# SCH_HABSat2_schematic_2023-01-31.net
KiCad netlist of a schematic drawn in EasyEDA
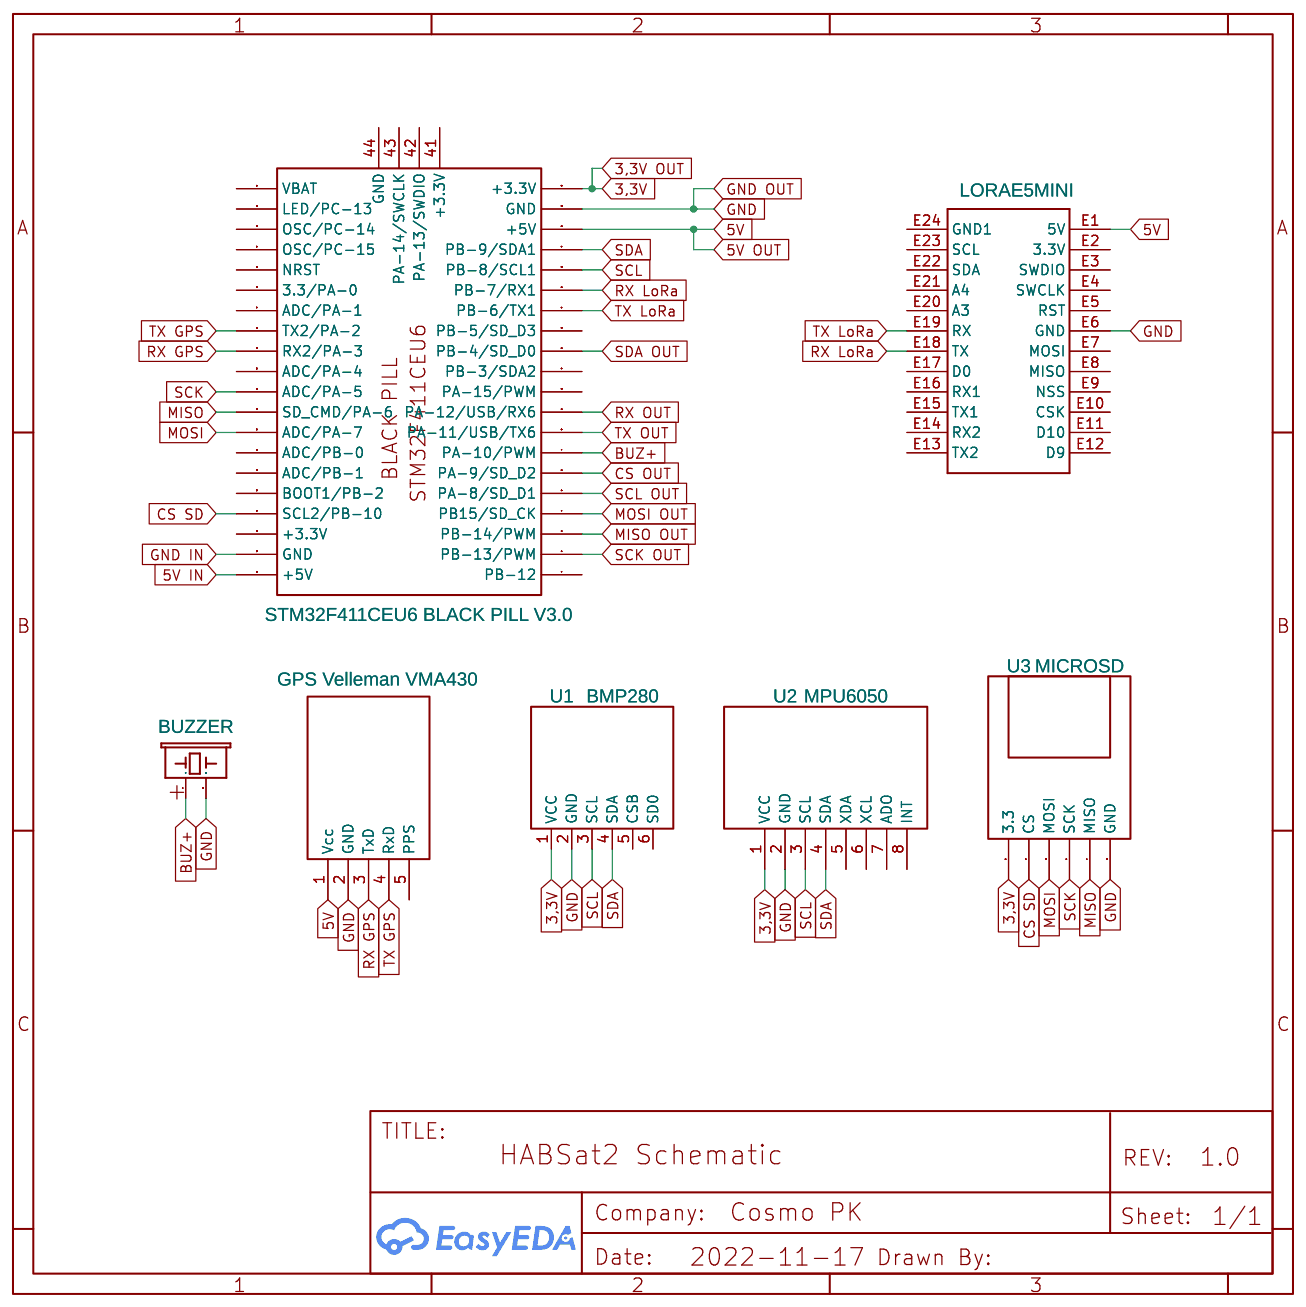
[diagram p0: schematic sheet]

(export (version "E")
  (design (tool "Eeschema 10.0.6"))
  (components
    (comp (ref "1") (value "LORAE5MINI") (libsource (lib "") (part "LORAE5MINI")))
    (comp (ref "SG1") (value "BUZZER") (libsource (lib "") (part "BUZZER KX-12MM")))
    (comp (ref "STM1")
      (value "STM32F411CEU6 BLACK PILL V3.0")
      (libsource (lib "") (part "STM32F411CEU6 BLACK PILL V3.0"))
    )
    (comp (ref "U1")
      (value "BMP280")
      (fields (field (name "BOM_Manufacturer Part") "GY-BMP280"))
      (libsource (lib "") (part "GY-BMP280"))
    )
    (comp (ref "U2") (value "MPU6050") (libsource (lib "") (part "MPU6050")))
    (comp (ref "U3") (value "MICROSD") (libsource (lib "") (part "MICROSD")))
    (comp (ref "VCC")
      (value "GPS Velleman VMA430")
      (fields (field (name "BOM_Manufacturer Part") "VMA430"))
      (libsource (lib "") (part "GPS Velleman VMA430"))
    )
  )
  (nets
    (net (code "1") (name "3,3V") (class "Default")
      (node (ref "STM1") (pin "20") (pinfunction "+3.3V_20") (pintype "unspecified"))
      (node (ref "U1") (pin "1") (pinfunction "VCC_1") (pintype "unspecified"))
      (node (ref "U2") (pin "1") (pinfunction "VCC_1") (pintype "unspecified"))
      (node (ref "U3") (pin "5") (pinfunction "3.3_5") (pintype "unspecified"))
    )
    (net (code "2") (name "5V") (class "Default")
      (node (ref "1") (pin "E1") (pinfunction "5V_E1") (pintype "bidirectional"))
      (node (ref "STM1") (pin "18") (pinfunction "+5V_18") (pintype "unspecified"))
      (node (ref "VCC") (pin "1") (pinfunction "Vcc_1") (pintype "unspecified"))
    )
    (net (code "3") (name "5V IN") (class "Default")
      (node (ref "STM1") (pin "40") (pinfunction "+5V_40") (pintype "unspecified"))
    )
    (net (code "4") (name "BUZ+") (class "Default")
      (node (ref "SG1") (pin "1") (pinfunction "1_1") (pintype "unspecified"))
      (node (ref "STM1") (pin "7") (pinfunction "PA-10/PWM_7") (pintype "unspecified"))
    )
    (net (code "5") (name "CS OUT") (class "Default")
      (node (ref "STM1") (pin "6") (pinfunction "PA-9/SD_D2_6") (pintype "unspecified"))
    )
    (net (code "6") (name "CS SD") (class "Default")
      (node (ref "STM1") (pin "37") (pinfunction "SCL2/PB-10_37") (pintype "unspecified"))
      (node (ref "U3") (pin "1") (pinfunction "CS_1") (pintype "unspecified"))
    )
    (net (code "7") (name "GND") (class "Default")
      (node (ref "1") (pin "E6") (pinfunction "GND_E6") (pintype "bidirectional"))
      (node (ref "SG1") (pin "2") (pinfunction "2_2") (pintype "unspecified"))
      (node (ref "STM1") (pin "19") (pinfunction "GND_19") (pintype "unspecified"))
      (node (ref "U1") (pin "2") (pinfunction "GND_2") (pintype "unspecified"))
      (node (ref "U2") (pin "2") (pinfunction "GND_2") (pintype "unspecified"))
      (node (ref "U3") (pin "6") (pinfunction "GND_6") (pintype "unspecified"))
      (node (ref "VCC") (pin "2") (pinfunction "GND_2") (pintype "unspecified"))
    )
    (net (code "8") (name "GND IN") (class "Default")
      (node (ref "STM1") (pin "39") (pinfunction "GND_39") (pintype "unspecified"))
    )
    (net (code "9") (name "MISO") (class "Default")
      (node (ref "STM1") (pin "32") (pinfunction "SD_CMD/PA-6_32") (pintype "unspecified"))
      (node (ref "U3") (pin "4") (pinfunction "MISO_4") (pintype "unspecified"))
    )
    (net (code "10") (name "MISO OUT") (class "Default")
      (node (ref "STM1") (pin "3") (pinfunction "PB-14/PWM_3") (pintype "unspecified"))
    )
    (net (code "11") (name "MOSI") (class "Default")
      (node (ref "STM1") (pin "33") (pinfunction "ADC/PA-7_33") (pintype "unspecified"))
      (node (ref "U3") (pin "3") (pinfunction "MOSI_3") (pintype "unspecified"))
    )
    (net (code "12") (name "MOSI OUT") (class "Default")
      (node (ref "STM1") (pin "4") (pinfunction "PB15/SD_CK_4") (pintype "unspecified"))
    )
    (net (code "13") (name "RX GPS") (class "Default")
      (node (ref "STM1") (pin "29") (pinfunction "RX2/PA-3_29") (pintype "unspecified"))
      (node (ref "VCC") (pin "3") (pinfunction "TxD_3") (pintype "unspecified"))
    )
    (net (code "14") (name "RX LoRa") (class "Default")
      (node (ref "1") (pin "E18") (pinfunction "TX_E18") (pintype "bidirectional"))
      (node (ref "STM1") (pin "15") (pinfunction "PB-7/RX1_15") (pintype "unspecified"))
    )
    (net (code "15") (name "RX OUT") (class "Default")
      (node (ref "STM1") (pin "9") (pinfunction "PA-12/USB/RX6_9") (pintype "unspecified"))
    )
    (net (code "16") (name "SCK") (class "Default")
      (node (ref "STM1") (pin "31") (pinfunction "ADC/PA-5_31") (pintype "unspecified"))
      (node (ref "U3") (pin "2") (pinfunction "SCK_2") (pintype "unspecified"))
    )
    (net (code "17") (name "SCK OUT") (class "Default")
      (node (ref "STM1") (pin "2") (pinfunction "PB-13/PWM_2") (pintype "unspecified"))
    )
    (net (code "18") (name "SCL") (class "Default")
      (node (ref "STM1") (pin "16") (pinfunction "PB-8/SCL1_16") (pintype "unspecified"))
      (node (ref "U1") (pin "3") (pinfunction "SCL_3") (pintype "unspecified"))
      (node (ref "U2") (pin "3") (pinfunction "SCL_3") (pintype "unspecified"))
    )
    (net (code "19") (name "SCL OUT") (class "Default")
      (node (ref "STM1") (pin "5") (pinfunction "PA-8/SD_D1_5") (pintype "unspecified"))
    )
    (net (code "20") (name "SDA") (class "Default")
      (node (ref "STM1") (pin "17") (pinfunction "PB-9/SDA1_17") (pintype "unspecified"))
      (node (ref "U1") (pin "4") (pinfunction "SDA_4") (pintype "unspecified"))
      (node (ref "U2") (pin "4") (pinfunction "SDA_4") (pintype "unspecified"))
    )
    (net (code "21") (name "SDA OUT") (class "Default")
      (node (ref "STM1") (pin "12") (pinfunction "PB-4/SD_D0_12") (pintype "unspecified"))
    )
    (net (code "22") (name "TX GPS") (class "Default")
      (node (ref "STM1") (pin "28") (pinfunction "TX2/PA-2_28") (pintype "unspecified"))
      (node (ref "VCC") (pin "4") (pinfunction "RxD_4") (pintype "unspecified"))
    )
    (net (code "23") (name "TX LoRa") (class "Default")
      (node (ref "1") (pin "E19") (pinfunction "RX_E19") (pintype "bidirectional"))
      (node (ref "STM1") (pin "14") (pinfunction "PB-6/TX1_14") (pintype "unspecified"))
    )
    (net (code "24") (name "TX OUT") (class "Default")
      (node (ref "STM1") (pin "8") (pinfunction "PA-11/USB/TX6_8") (pintype "unspecified"))
    )
    (net (code "25") (name "unconnected-(1-3.3V-PadE2)") (class "Default")
      (node (ref "1") (pin "E2") (pinfunction "3.3V_E2") (pintype "bidirectional"))
    )
    (net (code "26") (name "unconnected-(1-A3-PadE20)") (class "Default")
      (node (ref "1") (pin "E20") (pinfunction "A3_E20") (pintype "bidirectional"))
    )
    (net (code "27") (name "unconnected-(1-A4-PadE21)") (class "Default")
      (node (ref "1") (pin "E21") (pinfunction "A4_E21") (pintype "bidirectional"))
    )
    (net (code "28") (name "unconnected-(1-CSK-PadE10)") (class "Default")
      (node (ref "1") (pin "E10") (pinfunction "CSK_E10") (pintype "bidirectional"))
    )
    (net (code "29") (name "unconnected-(1-D0-PadE17)") (class "Default")
      (node (ref "1") (pin "E17") (pinfunction "D0_E17") (pintype "bidirectional"))
    )
    (net (code "30") (name "unconnected-(1-D9-PadE12)") (class "Default")
      (node (ref "1") (pin "E12") (pinfunction "D9_E12") (pintype "bidirectional"))
    )
    (net (code "31") (name "unconnected-(1-D10-PadE11)") (class "Default")
      (node (ref "1") (pin "E11") (pinfunction "D10_E11") (pintype "bidirectional"))
    )
    (net (code "32") (name "unconnected-(1-GND1-PadE24)") (class "Default")
      (node (ref "1") (pin "E24") (pinfunction "GND1_E24") (pintype "bidirectional"))
    )
    (net (code "33") (name "unconnected-(1-MISO-PadE8)") (class "Default")
      (node (ref "1") (pin "E8") (pinfunction "MISO_E8") (pintype "bidirectional"))
    )
    (net (code "34") (name "unconnected-(1-MOSI-PadE7)") (class "Default")
      (node (ref "1") (pin "E7") (pinfunction "MOSI_E7") (pintype "bidirectional"))
    )
    (net (code "35") (name "unconnected-(1-NSS-PadE9)") (class "Default")
      (node (ref "1") (pin "E9") (pinfunction "NSS_E9") (pintype "bidirectional"))
    )
    (net (code "36") (name "unconnected-(1-RST-PadE5)") (class "Default")
      (node (ref "1") (pin "E5") (pinfunction "RST_E5") (pintype "bidirectional"))
    )
    (net (code "37") (name "unconnected-(1-RX1-PadE16)") (class "Default")
      (node (ref "1") (pin "E16") (pinfunction "RX1_E16") (pintype "bidirectional"))
    )
    (net (code "38") (name "unconnected-(1-RX2-PadE14)") (class "Default")
      (node (ref "1") (pin "E14") (pinfunction "RX2_E14") (pintype "bidirectional"))
    )
    (net (code "39") (name "unconnected-(1-SCL-PadE23)") (class "Default")
      (node (ref "1") (pin "E23") (pinfunction "SCL_E23") (pintype "bidirectional"))
    )
    (net (code "40") (name "unconnected-(1-SDA-PadE22)") (class "Default")
      (node (ref "1") (pin "E22") (pinfunction "SDA_E22") (pintype "bidirectional"))
    )
    (net (code "41") (name "unconnected-(1-SWCLK-PadE4)") (class "Default")
      (node (ref "1") (pin "E4") (pinfunction "SWCLK_E4") (pintype "bidirectional"))
    )
    (net (code "42") (name "unconnected-(1-SWDIO-PadE3)") (class "Default")
      (node (ref "1") (pin "E3") (pinfunction "SWDIO_E3") (pintype "bidirectional"))
    )
    (net (code "43") (name "unconnected-(1-TX1-PadE15)") (class "Default")
      (node (ref "1") (pin "E15") (pinfunction "TX1_E15") (pintype "bidirectional"))
    )
    (net (code "44") (name "unconnected-(1-TX2-PadE13)") (class "Default")
      (node (ref "1") (pin "E13") (pinfunction "TX2_E13") (pintype "bidirectional"))
    )
    (net (code "45") (name "unconnected-(STM1-+3.3V-Pad38)") (class "Default")
      (node (ref "STM1") (pin "38") (pinfunction "+3.3V_38") (pintype "unspecified"))
    )
    (net (code "46") (name "unconnected-(STM1-+3.3V-Pad41)") (class "Default")
      (node (ref "STM1") (pin "41") (pinfunction "+3.3V_41") (pintype "unspecified"))
    )
    (net (code "47") (name "unconnected-(STM1-3.3{slash}PA-0-Pad26)") (class "Default")
      (node (ref "STM1") (pin "26") (pinfunction "3.3/PA-0_26") (pintype "unspecified"))
    )
    (net (code "48") (name "unconnected-(STM1-ADC{slash}PA-1-Pad27)") (class "Default")
      (node (ref "STM1") (pin "27") (pinfunction "ADC/PA-1_27") (pintype "unspecified"))
    )
    (net (code "49") (name "unconnected-(STM1-ADC{slash}PA-4-Pad30)") (class "Default")
      (node (ref "STM1") (pin "30") (pinfunction "ADC/PA-4_30") (pintype "unspecified"))
    )
    (net (code "50") (name "unconnected-(STM1-ADC{slash}PB-0-Pad34)") (class "Default")
      (node (ref "STM1") (pin "34") (pinfunction "ADC/PB-0_34") (pintype "unspecified"))
    )
    (net (code "51") (name "unconnected-(STM1-ADC{slash}PB-1-Pad35)") (class "Default")
      (node (ref "STM1") (pin "35") (pinfunction "ADC/PB-1_35") (pintype "unspecified"))
    )
    (net (code "52") (name "unconnected-(STM1-BOOT1{slash}PB-2-Pad36)") (class "Default")
      (node (ref "STM1") (pin "36") (pinfunction "BOOT1/PB-2_36") (pintype "unspecified"))
    )
    (net (code "53") (name "unconnected-(STM1-GND-Pad44)") (class "Default")
      (node (ref "STM1") (pin "44") (pinfunction "GND_44") (pintype "unspecified"))
    )
    (net (code "54") (name "unconnected-(STM1-LED{slash}PC-13-Pad22)") (class "Default")
      (node (ref "STM1") (pin "22") (pinfunction "LED/PC-13_22") (pintype "unspecified"))
    )
    (net (code "55") (name "unconnected-(STM1-NRST-Pad25)") (class "Default")
      (node (ref "STM1") (pin "25") (pinfunction "NRST_25") (pintype "unspecified"))
    )
    (net (code "56") (name "unconnected-(STM1-OSC{slash}PC-14-Pad23)") (class "Default")
      (node (ref "STM1") (pin "23") (pinfunction "OSC/PC-14_23") (pintype "unspecified"))
    )
    (net (code "57") (name "unconnected-(STM1-OSC{slash}PC-15-Pad24)") (class "Default")
      (node (ref "STM1") (pin "24") (pinfunction "OSC/PC-15_24") (pintype "unspecified"))
    )
    (net (code "58") (name "unconnected-(STM1-PA-13{slash}SWDIO-Pad42)") (class "Default")
      (node (ref "STM1") (pin "42") (pinfunction "PA-13/SWDIO_42") (pintype "unspecified"))
    )
    (net (code "59") (name "unconnected-(STM1-PA-14{slash}SWCLK-Pad43)") (class "Default")
      (node (ref "STM1") (pin "43") (pinfunction "PA-14/SWCLK_43") (pintype "unspecified"))
    )
    (net (code "60") (name "unconnected-(STM1-PA-15{slash}PWM-Pad10)") (class "Default")
      (node (ref "STM1") (pin "10") (pinfunction "PA-15/PWM_10") (pintype "unspecified"))
    )
    (net (code "61") (name "unconnected-(STM1-PB-3{slash}SDA2-Pad11)") (class "Default")
      (node (ref "STM1") (pin "11") (pinfunction "PB-3/SDA2_11") (pintype "unspecified"))
    )
    (net (code "62") (name "unconnected-(STM1-PB-5{slash}SD_D3-Pad13)") (class "Default")
      (node (ref "STM1") (pin "13") (pinfunction "PB-5/SD_D3_13") (pintype "unspecified"))
    )
    (net (code "63") (name "unconnected-(STM1-PB-12-Pad1)") (class "Default")
      (node (ref "STM1") (pin "1") (pinfunction "PB-12_1") (pintype "unspecified"))
    )
    (net (code "64") (name "unconnected-(STM1-VBAT-Pad21)") (class "Default")
      (node (ref "STM1") (pin "21") (pinfunction "VBAT_21") (pintype "unspecified"))
    )
    (net (code "65") (name "unconnected-(U1-CSB-Pad5)") (class "Default")
      (node (ref "U1") (pin "5") (pinfunction "CSB_5") (pintype "unspecified"))
    )
    (net (code "66") (name "unconnected-(U1-SD0-Pad6)") (class "Default")
      (node (ref "U1") (pin "6") (pinfunction "SD0_6") (pintype "unspecified"))
    )
    (net (code "67") (name "unconnected-(U2-ADO-Pad7)") (class "Default")
      (node (ref "U2") (pin "7") (pinfunction "ADO_7") (pintype "unspecified"))
    )
    (net (code "68") (name "unconnected-(U2-INT-Pad8)") (class "Default")
      (node (ref "U2") (pin "8") (pinfunction "INT_8") (pintype "unspecified"))
    )
    (net (code "69") (name "unconnected-(U2-XCL-Pad6)") (class "Default")
      (node (ref "U2") (pin "6") (pinfunction "XCL_6") (pintype "unspecified"))
    )
    (net (code "70") (name "unconnected-(U2-XDA-Pad5)") (class "Default")
      (node (ref "U2") (pin "5") (pinfunction "XDA_5") (pintype "unspecified"))
    )
    (net (code "71") (name "unconnected-(VCC-PPS-Pad5)") (class "Default")
      (node (ref "VCC") (pin "5") (pinfunction "PPS_5") (pintype "unspecified"))
    )
  )
)
